# color_proximity_sensor.net
KiCad netlist of a schematic drawn in EAGLE
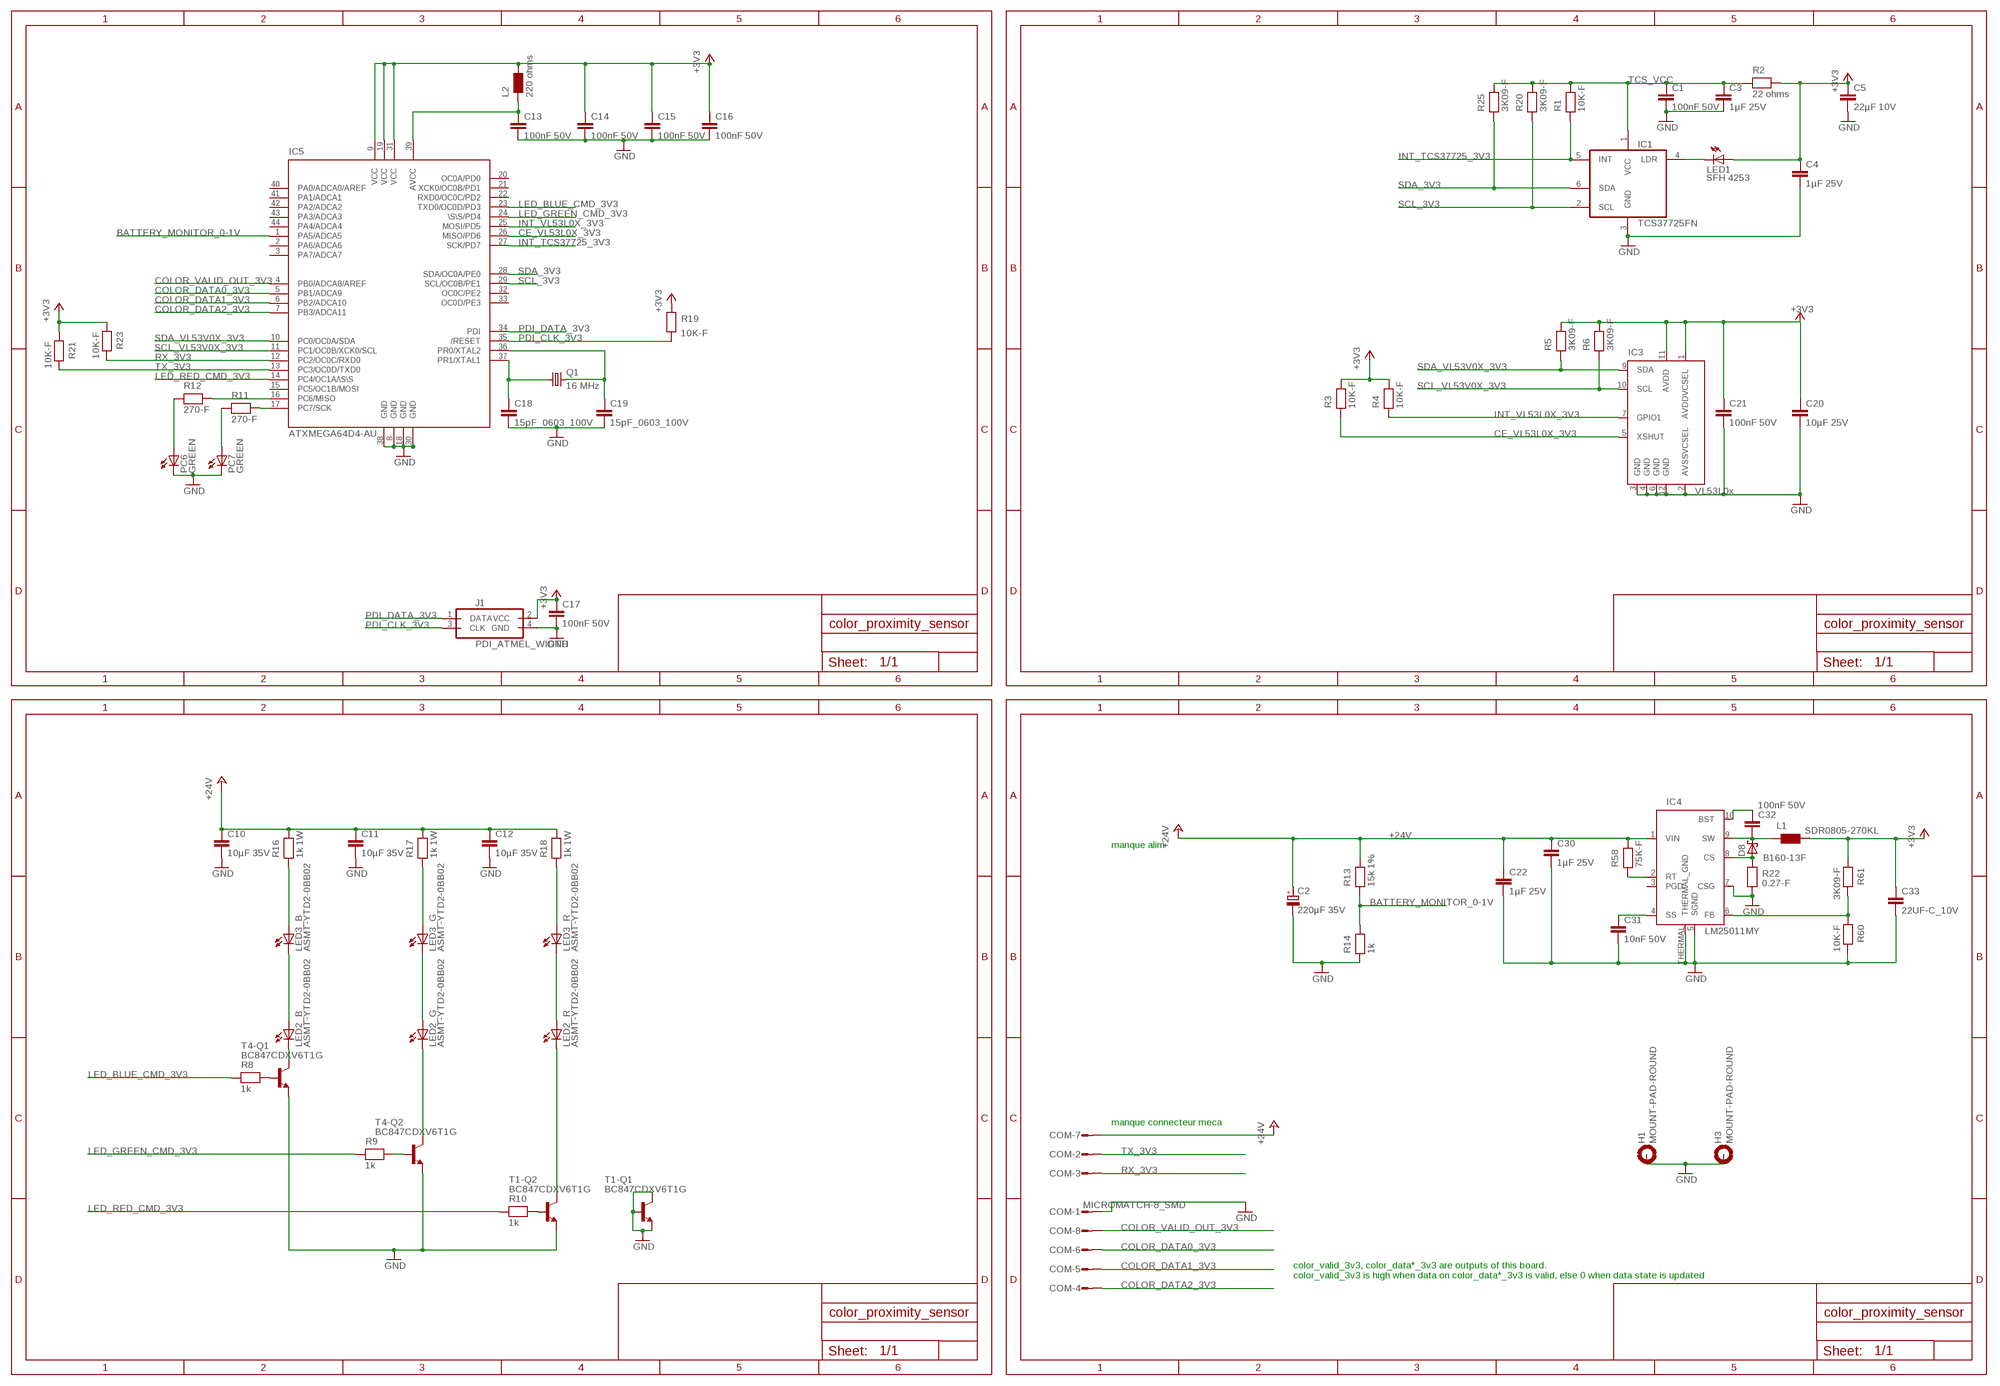
[diagram p0: schematic, sheet 1]

(export (version "E")
  (design (tool "Eeschema 10.0.6"))
  (components
    (comp (ref "C1")
      (value "100nF 50V")
      (footprint "eagle-import:C0603")
      (libsource (lib "eagle-import") (part "100NF-F"))
    )
    (comp (ref "C2")
      (value "220µF 35V")
      (footprint "eagle-import:PANASONIC_F")
      (libsource (lib "eagle-import") (part "220UFF_35V"))
    )
    (comp (ref "C3")
      (value "1µF 25V")
      (footprint "eagle-import:C1206")
      (libsource (lib "eagle-import") (part "1UFD_25V"))
    )
    (comp (ref "C4")
      (value "1µF 25V")
      (footprint "eagle-import:C1206")
      (libsource (lib "eagle-import") (part "1UFD_25V"))
    )
    (comp (ref "C5")
      (value "22µF 10V")
      (footprint "eagle-import:C1210")
      (libsource (lib "eagle-import") (part "22UF-C_10V"))
    )
    (comp (ref "C10")
      (value "10µF 35V")
      (footprint "eagle-import:C1210")
      (libsource (lib "eagle-import") (part "10UF-C_35V"))
    )
    (comp (ref "C11")
      (value "10µF 35V")
      (footprint "eagle-import:C1210")
      (libsource (lib "eagle-import") (part "10UF-C_35V"))
    )
    (comp (ref "C12")
      (value "10µF 35V")
      (footprint "eagle-import:C1210")
      (libsource (lib "eagle-import") (part "10UF-C_35V"))
    )
    (comp (ref "C13")
      (value "100nF 50V")
      (footprint "eagle-import:C0603")
      (libsource (lib "eagle-import") (part "100NF-F"))
    )
    (comp (ref "C14")
      (value "100nF 50V")
      (footprint "eagle-import:C0603")
      (libsource (lib "eagle-import") (part "100NF-F"))
    )
    (comp (ref "C15")
      (value "100nF 50V")
      (footprint "eagle-import:C0603")
      (libsource (lib "eagle-import") (part "100NF-F"))
    )
    (comp (ref "C16")
      (value "100nF 50V")
      (footprint "eagle-import:C0603")
      (libsource (lib "eagle-import") (part "100NF-F"))
    )
    (comp (ref "C17")
      (value "100nF 50V")
      (footprint "eagle-import:C0603")
      (libsource (lib "eagle-import") (part "100NF-F"))
    )
    (comp (ref "C18")
      (value "15pF_0603_100V")
      (footprint "eagle-import:C0603")
      (libsource (lib "eagle-import") (part "15PF-F"))
    )
    (comp (ref "C19")
      (value "15pF_0603_100V")
      (footprint "eagle-import:C0603")
      (libsource (lib "eagle-import") (part "15PF-F"))
    )
    (comp (ref "C20")
      (value "10µF 25V")
      (footprint "eagle-import:C1210")
      (libsource (lib "eagle-import") (part "10UF-C_25V"))
    )
    (comp (ref "C21")
      (value "100nF 50V")
      (footprint "eagle-import:C0603")
      (libsource (lib "eagle-import") (part "100NF-F"))
    )
    (comp (ref "C22")
      (value "1µF 25V")
      (footprint "eagle-import:C1206")
      (libsource (lib "eagle-import") (part "1UFD_25V"))
    )
    (comp (ref "C30")
      (value "1µF 25V")
      (footprint "eagle-import:C1206")
      (libsource (lib "eagle-import") (part "1UFD_25V"))
    )
    (comp (ref "C31")
      (value "10nF 50V")
      (footprint "eagle-import:C0603")
      (libsource (lib "eagle-import") (part "10NF-F"))
    )
    (comp (ref "C32")
      (value "100nF 50V")
      (footprint "eagle-import:C0603")
      (libsource (lib "eagle-import") (part "100NF-F"))
    )
    (comp (ref "C33")
      (value "22UF-C_10V")
      (footprint "eagle-import:C1210")
      (libsource (lib "eagle-import") (part "22UF-C_10V"))
    )
    (comp (ref "COM")
      (value "MICROMATCH-8_SMD")
      (footprint "eagle-import:MICROMATCH-8_SMD")
      (libsource (lib "eagle-import") (part "MICROMATCH-8_SMD"))
    )
    (comp (ref "D8")
      (value "B160-13F")
      (footprint "eagle-import:SMA")
      (libsource (lib "eagle-import") (part "B160-13F"))
    )
    (comp (ref "H1")
      (value "MOUNT-PAD-ROUND")
      (footprint "eagle-import:2,1-PAD")
      (libsource (lib "eagle-import") (part "MOUNT-PAD-ROUND"))
    )
    (comp (ref "H3")
      (value "MOUNT-PAD-ROUND")
      (footprint "eagle-import:2,1-PAD")
      (libsource (lib "eagle-import") (part "MOUNT-PAD-ROUND"))
    )
    (comp (ref "IC1")
      (value "TCS37725FN")
      (footprint "eagle-import:FN6")
      (libsource (lib "eagle-import") (part "TCS37725FN"))
    )
    (comp (ref "IC3")
      (value "VL53L0x")
      (footprint "eagle-import:LGA12")
      (libsource (lib "eagle-import") (part "VL53L0X"))
    )
    (comp (ref "IC4")
      (value "LM25011MY")
      (footprint "eagle-import:MSOP10_THERMAL")
      (libsource (lib "eagle-import") (part "LM25011MY"))
    )
    (comp (ref "IC5")
      (value "ATXMEGA64D4-AU")
      (footprint "eagle-import:TQFP44")
      (libsource (lib "eagle-import") (part "ATXMEGA64D4-AU"))
    )
    (comp (ref "J1")
      (value "PDI_ATMEL_WIDTH")
      (footprint "eagle-import:HEADER_2.54MM_2X2W_")
      (libsource (lib "eagle-import") (part "PDI_ATMEL_WIDTH"))
    )
    (comp (ref "L1")
      (value "SDR0805-270KL")
      (footprint "eagle-import:SDR0805")
      (libsource (lib "eagle-import") (part "SDR0805-270KL"))
    )
    (comp (ref "L2")
      (value "220 ohms")
      (footprint "eagle-import:R0603")
      (libsource (lib "eagle-import") (part "FERRITE_220OHMS"))
    )
    (comp (ref "LED1")
      (value "SFH 4253")
      (footprint "eagle-import:SFH4253")
      (libsource (lib "eagle-import") (part "SFH4253"))
    )
    (comp (ref "LED2")
      (value "ASMT-YTD2-0BB02")
      (footprint "eagle-import:PLCC6")
      (fields (field (name "MANUFACTURER") "AVAGO TECHNOLOGIES"))
      (libsource (lib "eagle-import") (part "LED_MULTICOLOR"))
    )
    (comp (ref "LED3")
      (value "ASMT-YTD2-0BB02")
      (footprint "eagle-import:PLCC6")
      (fields (field (name "MANUFACTURER") "AVAGO TECHNOLOGIES"))
      (libsource (lib "eagle-import") (part "LED_MULTICOLOR"))
    )
    (comp (ref "PC6")
      (value "GREEN")
      (footprint "eagle-import:CHIP-LED0805")
      (libsource (lib "eagle-import") (part "LED_G"))
    )
    (comp (ref "PC7")
      (value "GREEN")
      (footprint "eagle-import:CHIP-LED0805")
      (libsource (lib "eagle-import") (part "LED_G"))
    )
    (comp (ref "Q1")
      (value "16 MHz")
      (footprint "eagle-import:HC49UP")
      (libsource (lib "eagle-import") (part "CRYSTAL_16MHZ_HC49UP"))
    )
    (comp (ref "R1")
      (value "10K-F")
      (footprint "eagle-import:R0603")
      (libsource (lib "eagle-import") (part "10K-F"))
    )
    (comp (ref "R2")
      (value "22 ohms")
      (footprint "eagle-import:R0603")
      (libsource (lib "eagle-import") (part "22-F"))
    )
    (comp (ref "R3")
      (value "10K-F")
      (footprint "eagle-import:R0603")
      (libsource (lib "eagle-import") (part "10K-F"))
    )
    (comp (ref "R4")
      (value "10K-F")
      (footprint "eagle-import:R0603")
      (libsource (lib "eagle-import") (part "10K-F"))
    )
    (comp (ref "R5")
      (value "3K09-F")
      (footprint "eagle-import:R0603")
      (libsource (lib "eagle-import") (part "3K09-F"))
    )
    (comp (ref "R6")
      (value "3K09-F")
      (footprint "eagle-import:R0603")
      (libsource (lib "eagle-import") (part "3K09-F"))
    )
    (comp (ref "R8")
      (value "1k")
      (footprint "eagle-import:R0603")
      (libsource (lib "eagle-import") (part "1K-F"))
    )
    (comp (ref "R9")
      (value "1k")
      (footprint "eagle-import:R0603")
      (libsource (lib "eagle-import") (part "1K-F"))
    )
    (comp (ref "R10")
      (value "1k")
      (footprint "eagle-import:R0603")
      (libsource (lib "eagle-import") (part "1K-F"))
    )
    (comp (ref "R11")
      (value "270-F")
      (footprint "eagle-import:R0603")
      (libsource (lib "eagle-import") (part "270-F"))
    )
    (comp (ref "R12")
      (value "270-F")
      (footprint "eagle-import:R0603")
      (libsource (lib "eagle-import") (part "270-F"))
    )
    (comp (ref "R13")
      (value "15k 1%")
      (footprint "eagle-import:R0805")
      (libsource (lib "eagle-import") (part "15K-E"))
    )
    (comp (ref "R14")
      (value "1k")
      (footprint "eagle-import:R0805")
      (libsource (lib "eagle-import") (part "1K-E"))
    )
    (comp (ref "R16")
      (value "1k 1W")
      (footprint "eagle-import:R2512")
      (libsource (lib "eagle-import") (part "1K-A"))
    )
    (comp (ref "R17")
      (value "1k 1W")
      (footprint "eagle-import:R2512")
      (libsource (lib "eagle-import") (part "1K-A"))
    )
    (comp (ref "R18")
      (value "1k 1W")
      (footprint "eagle-import:R2512")
      (libsource (lib "eagle-import") (part "1K-A"))
    )
    (comp (ref "R19")
      (value "10K-F")
      (footprint "eagle-import:R0603")
      (libsource (lib "eagle-import") (part "10K-F"))
    )
    (comp (ref "R20")
      (value "3K09-F")
      (footprint "eagle-import:R0603")
      (libsource (lib "eagle-import") (part "3K09-F"))
    )
    (comp (ref "R21")
      (value "10K-F")
      (footprint "eagle-import:R0603")
      (libsource (lib "eagle-import") (part "10K-F"))
    )
    (comp (ref "R22")
      (value "0.27-F")
      (footprint "eagle-import:R0603")
      (libsource (lib "eagle-import") (part "0.27-F"))
    )
    (comp (ref "R23")
      (value "10K-F")
      (footprint "eagle-import:R0603")
      (libsource (lib "eagle-import") (part "10K-F"))
    )
    (comp (ref "R25")
      (value "3K09-F")
      (footprint "eagle-import:R0603")
      (libsource (lib "eagle-import") (part "3K09-F"))
    )
    (comp (ref "R58")
      (value "75K-F")
      (footprint "eagle-import:R0603")
      (libsource (lib "eagle-import") (part "75K-F"))
    )
    (comp (ref "R60")
      (value "10K-F")
      (footprint "eagle-import:R0603")
      (libsource (lib "eagle-import") (part "10K-F"))
    )
    (comp (ref "R61")
      (value "3K09-F")
      (footprint "eagle-import:R0603")
      (libsource (lib "eagle-import") (part "3K09-F"))
    )
    (comp (ref "T1")
      (value "BC847CDXV6T1G")
      (footprint "eagle-import:SOT563-6")
      (libsource (lib "eagle-import") (part "BC847CDXV6T"))
    )
    (comp (ref "T4")
      (value "BC847CDXV6T1G")
      (footprint "eagle-import:SOT563-6")
      (libsource (lib "eagle-import") (part "BC847CDXV6T"))
    )
  )
  (nets
    (net (code "1") (name "+3V3") (class "Default")
      (node (ref "C14") (pin "1") (pinfunction "1_1") (pintype "passive"))
      (node (ref "C15") (pin "1") (pinfunction "1_1") (pintype "passive"))
      (node (ref "C16") (pin "1") (pinfunction "1_1") (pintype "passive"))
      (node (ref "C17") (pin "1") (pinfunction "1_1") (pintype "passive"))
      (node (ref "C20") (pin "1") (pinfunction "1_1") (pintype "passive"))
      (node (ref "C21") (pin "1") (pinfunction "1_1") (pintype "passive"))
      (node (ref "C33") (pin "1") (pinfunction "1_1") (pintype "passive"))
      (node (ref "C4") (pin "1") (pinfunction "1_1") (pintype "passive"))
      (node (ref "C5") (pin "1") (pinfunction "1_1") (pintype "passive"))
      (node (ref "IC3") (pin "1") (pinfunction "AVDDVCSEL_1") (pintype "power_in"))
      (node (ref "IC3") (pin "11") (pinfunction "AVDD_11") (pintype "bidirectional"))
      (node (ref "IC5") (pin "19") (pinfunction "VCC_19") (pintype "bidirectional"))
      (node (ref "IC5") (pin "31") (pinfunction "VCC_31") (pintype "bidirectional"))
      (node (ref "IC5") (pin "9") (pinfunction "VCC_9") (pintype "bidirectional"))
      (node (ref "J1") (pin "2") (pinfunction "VCC_2") (pintype "passive"))
      (node (ref "L1") (pin "2") (pinfunction "2_2") (pintype "passive"))
      (node (ref "L2") (pin "2") (pinfunction "2_2") (pintype "passive"))
      (node (ref "LED1") (pin "A") (pinfunction "A_A") (pintype "passive"))
      (node (ref "R19") (pin "2") (pinfunction "2_2") (pintype "bidirectional"))
      (node (ref "R2") (pin "2") (pinfunction "2_2") (pintype "bidirectional"))
      (node (ref "R21") (pin "1") (pinfunction "1_1") (pintype "bidirectional"))
      (node (ref "R23") (pin "1") (pinfunction "1_1") (pintype "bidirectional"))
      (node (ref "R3") (pin "2") (pinfunction "2_2") (pintype "bidirectional"))
      (node (ref "R4") (pin "2") (pinfunction "2_2") (pintype "bidirectional"))
      (node (ref "R5") (pin "2") (pinfunction "2_2") (pintype "bidirectional"))
      (node (ref "R6") (pin "2") (pinfunction "2_2") (pintype "bidirectional"))
      (node (ref "R61") (pin "1") (pinfunction "1_1") (pintype "bidirectional"))
    )
    (net (code "2") (name "+24V") (class "Default")
      (node (ref "C10") (pin "1") (pinfunction "1_1") (pintype "passive"))
      (node (ref "C11") (pin "1") (pinfunction "1_1") (pintype "passive"))
      (node (ref "C12") (pin "1") (pinfunction "1_1") (pintype "passive"))
      (node (ref "C2") (pin "+") (pinfunction "+_+") (pintype "passive"))
      (node (ref "C22") (pin "1") (pinfunction "1_1") (pintype "passive"))
      (node (ref "C30") (pin "1") (pinfunction "1_1") (pintype "passive"))
      (node (ref "COM") (pin "7") (pinfunction "S_7") (pintype "passive"))
      (node (ref "IC4") (pin "1") (pinfunction "VIN_1") (pintype "input"))
      (node (ref "R13") (pin "2") (pinfunction "2_2") (pintype "bidirectional"))
      (node (ref "R16") (pin "2") (pinfunction "2_2") (pintype "bidirectional"))
      (node (ref "R17") (pin "2") (pinfunction "2_2") (pintype "bidirectional"))
      (node (ref "R18") (pin "2") (pinfunction "2_2") (pintype "bidirectional"))
      (node (ref "R58") (pin "2") (pinfunction "2_2") (pintype "bidirectional"))
    )
    (net (code "3") (name "/BATTERY_MONITOR_0-1V") (class "Default")
      (node (ref "IC5") (pin "1") (pinfunction "PA5/ADCA5_1") (pintype "bidirectional"))
      (node (ref "R13") (pin "1") (pinfunction "1_1") (pintype "bidirectional"))
      (node (ref "R14") (pin "2") (pinfunction "2_2") (pintype "bidirectional"))
    )
    (net (code "4") (name "/CE_VL53L0X_3V3") (class "Default")
      (node (ref "IC3") (pin "5") (pinfunction "XSHUT_5") (pintype "bidirectional"))
      (node (ref "IC5") (pin "26") (pinfunction "MISO/PD6_26") (pintype "bidirectional"))
      (node (ref "R3") (pin "1") (pinfunction "1_1") (pintype "bidirectional"))
    )
    (net (code "5") (name "/COLOR_DATA0_3V3") (class "Default")
      (node (ref "COM") (pin "6") (pinfunction "S_6") (pintype "passive"))
      (node (ref "IC5") (pin "5") (pinfunction "PB1/ADCA9_5") (pintype "bidirectional"))
    )
    (net (code "6") (name "/COLOR_DATA1_3V3") (class "Default")
      (node (ref "COM") (pin "5") (pinfunction "S_5") (pintype "passive"))
      (node (ref "IC5") (pin "6") (pinfunction "PB2/ADCA10_6") (pintype "bidirectional"))
    )
    (net (code "7") (name "/COLOR_DATA2_3V3") (class "Default")
      (node (ref "COM") (pin "4") (pinfunction "S_4") (pintype "passive"))
      (node (ref "IC5") (pin "7") (pinfunction "PB3/ADCA11_7") (pintype "bidirectional"))
    )
    (net (code "8") (name "/COLOR_VALID_OUT_3V3") (class "Default")
      (node (ref "COM") (pin "8") (pinfunction "S_8") (pintype "passive"))
      (node (ref "IC5") (pin "4") (pinfunction "PB0/ADCA8/AREF_4") (pintype "bidirectional"))
    )
    (net (code "9") (name "/INT_TCS37725_3V3") (class "Default")
      (node (ref "IC1") (pin "5") (pinfunction "INT_5") (pintype "open_collector"))
      (node (ref "IC5") (pin "27") (pinfunction "SCK/PD7_27") (pintype "bidirectional"))
      (node (ref "R1") (pin "1") (pinfunction "1_1") (pintype "bidirectional"))
    )
    (net (code "10") (name "/INT_VL53L0X_3V3") (class "Default")
      (node (ref "IC3") (pin "7") (pinfunction "GPIO1_7") (pintype "output"))
      (node (ref "IC5") (pin "25") (pinfunction "MOSI/PD5_25") (pintype "bidirectional"))
      (node (ref "R4") (pin "1") (pinfunction "1_1") (pintype "bidirectional"))
    )
    (net (code "11") (name "/LED_BLUE_CMD_3V3") (class "Default")
      (node (ref "IC5") (pin "23") (pinfunction "TXD0/OC0D/PD3_23") (pintype "bidirectional"))
      (node (ref "R8") (pin "1") (pinfunction "1_1") (pintype "bidirectional"))
    )
    (net (code "12") (name "/LED_GREEN_CMD_3V3") (class "Default")
      (node (ref "IC5") (pin "24") (pinfunction "\\S\\S/PD4_24") (pintype "bidirectional"))
      (node (ref "R9") (pin "1") (pinfunction "1_1") (pintype "bidirectional"))
    )
    (net (code "13") (name "/LED_RED_CMD_3V3") (class "Default")
      (node (ref "IC5") (pin "14") (pinfunction "PC4/OC1A/\\S\\S_14") (pintype "bidirectional"))
      (node (ref "R10") (pin "1") (pinfunction "1_1") (pintype "bidirectional"))
    )
    (net (code "14") (name "/PDI_CLK_3V3") (class "Default")
      (node (ref "IC5") (pin "35") (pinfunction "/RESET_35") (pintype "bidirectional"))
      (node (ref "J1") (pin "3") (pinfunction "CLK_3") (pintype "passive"))
      (node (ref "R19") (pin "1") (pinfunction "1_1") (pintype "bidirectional"))
    )
    (net (code "15") (name "/PDI_DATA_3V3") (class "Default")
      (node (ref "IC5") (pin "34") (pinfunction "PDI_34") (pintype "bidirectional"))
      (node (ref "J1") (pin "1") (pinfunction "DATA_1") (pintype "passive"))
    )
    (net (code "16") (name "/RX_3V3") (class "Default")
      (node (ref "COM") (pin "3") (pinfunction "S_3") (pintype "passive"))
      (node (ref "IC5") (pin "12") (pinfunction "PC2/OC0C/RXD0_12") (pintype "bidirectional"))
      (node (ref "R23") (pin "2") (pinfunction "2_2") (pintype "bidirectional"))
    )
    (net (code "17") (name "/SCL_3V3") (class "Default")
      (node (ref "IC1") (pin "2") (pinfunction "SCL_2") (pintype "open_collector"))
      (node (ref "IC5") (pin "29") (pinfunction "SCL/OC0B/PE1_29") (pintype "bidirectional"))
      (node (ref "R20") (pin "1") (pinfunction "1_1") (pintype "bidirectional"))
    )
    (net (code "18") (name "/SCL_VL53V0X_3V3") (class "Default")
      (node (ref "IC3") (pin "10") (pinfunction "SCL_10") (pintype "input"))
      (node (ref "IC5") (pin "11") (pinfunction "PC1/OC0B/XCK0/SCL_11") (pintype "bidirectional"))
      (node (ref "R6") (pin "1") (pinfunction "1_1") (pintype "bidirectional"))
    )
    (net (code "19") (name "/SDA_3V3") (class "Default")
      (node (ref "IC1") (pin "6") (pinfunction "SDA_6") (pintype "open_collector"))
      (node (ref "IC5") (pin "28") (pinfunction "SDA/OC0A/PE0_28") (pintype "bidirectional"))
      (node (ref "R25") (pin "1") (pinfunction "1_1") (pintype "bidirectional"))
    )
    (net (code "20") (name "/SDA_VL53V0X_3V3") (class "Default")
      (node (ref "IC3") (pin "9") (pinfunction "SDA_9") (pintype "bidirectional"))
      (node (ref "IC5") (pin "10") (pinfunction "PC0/OC0A/SDA_10") (pintype "bidirectional"))
      (node (ref "R5") (pin "1") (pinfunction "1_1") (pintype "bidirectional"))
    )
    (net (code "21") (name "/TCS_VCC") (class "Default")
      (node (ref "C1") (pin "1") (pinfunction "1_1") (pintype "passive"))
      (node (ref "C3") (pin "1") (pinfunction "1_1") (pintype "passive"))
      (node (ref "IC1") (pin "1") (pinfunction "VCC_1") (pintype "power_in"))
      (node (ref "R1") (pin "2") (pinfunction "2_2") (pintype "bidirectional"))
      (node (ref "R2") (pin "1") (pinfunction "1_1") (pintype "bidirectional"))
      (node (ref "R20") (pin "2") (pinfunction "2_2") (pintype "bidirectional"))
      (node (ref "R25") (pin "2") (pinfunction "2_2") (pintype "bidirectional"))
    )
    (net (code "22") (name "/TX_3V3") (class "Default")
      (node (ref "COM") (pin "2") (pinfunction "S_2") (pintype "passive"))
      (node (ref "IC5") (pin "13") (pinfunction "PC3/OC0D/TXD0_13") (pintype "bidirectional"))
      (node (ref "R21") (pin "2") (pinfunction "2_2") (pintype "bidirectional"))
    )
    (net (code "23") (name "GND") (class "Default")
      (node (ref "C1") (pin "2") (pinfunction "2_2") (pintype "passive"))
      (node (ref "C10") (pin "2") (pinfunction "2_2") (pintype "passive"))
      (node (ref "C11") (pin "2") (pinfunction "2_2") (pintype "passive"))
      (node (ref "C12") (pin "2") (pinfunction "2_2") (pintype "passive"))
      (node (ref "C13") (pin "2") (pinfunction "2_2") (pintype "passive"))
      (node (ref "C14") (pin "2") (pinfunction "2_2") (pintype "passive"))
      (node (ref "C15") (pin "2") (pinfunction "2_2") (pintype "passive"))
      (node (ref "C16") (pin "2") (pinfunction "2_2") (pintype "passive"))
      (node (ref "C17") (pin "2") (pinfunction "2_2") (pintype "passive"))
      (node (ref "C18") (pin "2") (pinfunction "2_2") (pintype "passive"))
      (node (ref "C19") (pin "2") (pinfunction "2_2") (pintype "passive"))
      (node (ref "C2") (pin "-") (pinfunction "-_-") (pintype "passive"))
      (node (ref "C20") (pin "2") (pinfunction "2_2") (pintype "passive"))
      (node (ref "C21") (pin "2") (pinfunction "2_2") (pintype "passive"))
      (node (ref "C22") (pin "2") (pinfunction "2_2") (pintype "passive"))
      (node (ref "C3") (pin "2") (pinfunction "2_2") (pintype "passive"))
      (node (ref "C30") (pin "2") (pinfunction "2_2") (pintype "passive"))
      (node (ref "C31") (pin "2") (pinfunction "2_2") (pintype "passive"))
      (node (ref "C33") (pin "2") (pinfunction "2_2") (pintype "passive"))
      (node (ref "C4") (pin "2") (pinfunction "2_2") (pintype "passive"))
      (node (ref "C5") (pin "2") (pinfunction "2_2") (pintype "passive"))
      (node (ref "COM") (pin "1") (pinfunction "S_1") (pintype "passive"))
      (node (ref "H1") (pin "B2,8") (pinfunction "MOUNT_B2,8") (pintype "passive"))
      (node (ref "H3") (pin "B2,8") (pinfunction "MOUNT_B2,8") (pintype "passive"))
      (node (ref "IC1") (pin "3") (pinfunction "GND_3") (pintype "power_in"))
      (node (ref "IC3") (pin "12") (pinfunction "GND_12") (pintype "bidirectional"))
      (node (ref "IC3") (pin "2") (pinfunction "AVSSVCSEL_2") (pintype "power_in"))
      (node (ref "IC3") (pin "3") (pinfunction "GND_3") (pintype "bidirectional"))
      (node (ref "IC3") (pin "4") (pinfunction "GND_4") (pintype "bidirectional"))
      (node (ref "IC3") (pin "6") (pinfunction "GND_6") (pintype "bidirectional"))
      (node (ref "IC4") (pin "5") (pinfunction "SGND_5") (pintype "power_in"))
      (node (ref "IC4") (pin "7") (pinfunction "CSG_7") (pintype "input"))
      (node (ref "IC4") (pin "THERMAL") (pinfunction "THERMAL_GND_THERMAL") (pintype "power_in"))
      (node (ref "IC5") (pin "18") (pinfunction "GND_18") (pintype "bidirectional"))
      (node (ref "IC5") (pin "30") (pinfunction "GND_30") (pintype "bidirectional"))
      (node (ref "IC5") (pin "38") (pinfunction "GND_38") (pintype "bidirectional"))
      (node (ref "IC5") (pin "8") (pinfunction "GND_8") (pintype "bidirectional"))
      (node (ref "J1") (pin "4") (pinfunction "GND_4") (pintype "passive"))
      (node (ref "PC6") (pin "C") (pinfunction "C_C") (pintype "passive"))
      (node (ref "PC7") (pin "C") (pinfunction "C_C") (pintype "passive"))
      (node (ref "R14") (pin "1") (pinfunction "1_1") (pintype "bidirectional"))
      (node (ref "R22") (pin "1") (pinfunction "1_1") (pintype "bidirectional"))
      (node (ref "R60") (pin "2") (pinfunction "2_2") (pintype "bidirectional"))
      (node (ref "T1") (pin "1") (pinfunction "E_1") (pintype "passive"))
      (node (ref "T1") (pin "3") (pinfunction "C_3") (pintype "passive"))
      (node (ref "T1") (pin "4") (pinfunction "E_4") (pintype "passive"))
      (node (ref "T1") (pin "5") (pinfunction "B_5") (pintype "passive"))
      (node (ref "T4") (pin "1") (pinfunction "E_1") (pintype "passive"))
      (node (ref "T4") (pin "4") (pinfunction "E_4") (pintype "passive"))
    )
    (net (code "24") (name "Net-(IC1-LDR)") (class "Default")
      (node (ref "IC1") (pin "4") (pinfunction "LDR_4") (pintype "output"))
      (node (ref "LED1") (pin "C") (pinfunction "C_C") (pintype "passive"))
    )
    (net (code "25") (name "Net-(IC4-BST)") (class "Default")
      (node (ref "C32") (pin "1") (pinfunction "1_1") (pintype "passive"))
      (node (ref "IC4") (pin "10") (pinfunction "BST_10") (pintype "input"))
    )
    (net (code "26") (name "Net-(IC4-CS)") (class "Default")
      (node (ref "D8") (pin "A") (pinfunction "A_A") (pintype "passive"))
      (node (ref "IC4") (pin "8") (pinfunction "CS_8") (pintype "output"))
      (node (ref "R22") (pin "2") (pinfunction "2_2") (pintype "bidirectional"))
    )
    (net (code "27") (name "Net-(IC4-FB)") (class "Default")
      (node (ref "IC4") (pin "6") (pinfunction "FB_6") (pintype "input"))
      (node (ref "R60") (pin "1") (pinfunction "1_1") (pintype "bidirectional"))
      (node (ref "R61") (pin "2") (pinfunction "2_2") (pintype "bidirectional"))
    )
    (net (code "28") (name "Net-(IC4-RT)") (class "Default")
      (node (ref "IC4") (pin "2") (pinfunction "RT_2") (pintype "input"))
      (node (ref "R58") (pin "1") (pinfunction "1_1") (pintype "bidirectional"))
    )
    (net (code "29") (name "Net-(IC4-SS)") (class "Default")
      (node (ref "C31") (pin "1") (pinfunction "1_1") (pintype "passive"))
      (node (ref "IC4") (pin "4") (pinfunction "SS_4") (pintype "power_in"))
    )
    (net (code "30") (name "Net-(IC4-SW)") (class "Default")
      (node (ref "C32") (pin "2") (pinfunction "2_2") (pintype "passive"))
      (node (ref "D8") (pin "C") (pinfunction "C_C") (pintype "passive"))
      (node (ref "IC4") (pin "9") (pinfunction "SW_9") (pintype "output"))
      (node (ref "L1") (pin "1") (pinfunction "1_1") (pintype "passive"))
    )
    (net (code "31") (name "Net-(IC5-AVCC)") (class "Default")
      (node (ref "C13") (pin "1") (pinfunction "1_1") (pintype "passive"))
      (node (ref "IC5") (pin "39") (pinfunction "AVCC_39") (pintype "bidirectional"))
      (node (ref "L2") (pin "1") (pinfunction "1_1") (pintype "passive"))
    )
    (net (code "32") (name "Net-(IC5-PC6{slash}MISO)") (class "Default")
      (node (ref "IC5") (pin "16") (pinfunction "PC6/MISO_16") (pintype "bidirectional"))
      (node (ref "R12") (pin "2") (pinfunction "2_2") (pintype "bidirectional"))
    )
    (net (code "33") (name "Net-(IC5-PC7{slash}SCK)") (class "Default")
      (node (ref "IC5") (pin "17") (pinfunction "PC7/SCK_17") (pintype "bidirectional"))
      (node (ref "R11") (pin "2") (pinfunction "2_2") (pintype "bidirectional"))
    )
    (net (code "34") (name "Net-(IC5-PR0{slash}XTAL2)") (class "Default")
      (node (ref "C19") (pin "1") (pinfunction "1_1") (pintype "passive"))
      (node (ref "IC5") (pin "36") (pinfunction "PR0/XTAL2_36") (pintype "bidirectional"))
      (node (ref "Q1") (pin "2") (pinfunction "2_2") (pintype "passive"))
    )
    (net (code "35") (name "Net-(IC5-PR1{slash}XTAL1)") (class "Default")
      (node (ref "C18") (pin "1") (pinfunction "1_1") (pintype "passive"))
      (node (ref "IC5") (pin "37") (pinfunction "PR1/XTAL1_37") (pintype "bidirectional"))
      (node (ref "Q1") (pin "1") (pinfunction "1_1") (pintype "passive"))
    )
    (net (code "36") (name "Net-(LED2A-A)") (class "Default")
      (node (ref "LED2") (pin "6") (pinfunction "A_6") (pintype "passive"))
      (node (ref "LED3") (pin "1") (pinfunction "C_1") (pintype "passive"))
    )
    (net (code "37") (name "Net-(LED2A-C)") (class "Default")
      (node (ref "LED2") (pin "1") (pinfunction "C_1") (pintype "passive"))
      (node (ref "T4") (pin "3") (pinfunction "C_3") (pintype "passive"))
    )
    (net (code "38") (name "Net-(LED2B-A)") (class "Default")
      (node (ref "LED2") (pin "5") (pinfunction "A_5") (pintype "passive"))
      (node (ref "LED3") (pin "2") (pinfunction "C_2") (pintype "passive"))
    )
    (net (code "39") (name "Net-(LED2B-C)") (class "Default")
      (node (ref "LED2") (pin "2") (pinfunction "C_2") (pintype "passive"))
      (node (ref "T4") (pin "6") (pinfunction "C_6") (pintype "passive"))
    )
    (net (code "40") (name "Net-(LED2C-A)") (class "Default")
      (node (ref "LED2") (pin "4") (pinfunction "A_4") (pintype "passive"))
      (node (ref "LED3") (pin "3") (pinfunction "C_3") (pintype "passive"))
    )
    (net (code "41") (name "Net-(LED2C-C)") (class "Default")
      (node (ref "LED2") (pin "3") (pinfunction "C_3") (pintype "passive"))
      (node (ref "T1") (pin "6") (pinfunction "C_6") (pintype "passive"))
    )
    (net (code "42") (name "Net-(LED3A-A)") (class "Default")
      (node (ref "LED3") (pin "6") (pinfunction "A_6") (pintype "passive"))
      (node (ref "R16") (pin "1") (pinfunction "1_1") (pintype "bidirectional"))
    )
    (net (code "43") (name "Net-(LED3B-A)") (class "Default")
      (node (ref "LED3") (pin "5") (pinfunction "A_5") (pintype "passive"))
      (node (ref "R17") (pin "1") (pinfunction "1_1") (pintype "bidirectional"))
    )
    (net (code "44") (name "Net-(LED3C-A)") (class "Default")
      (node (ref "LED3") (pin "4") (pinfunction "A_4") (pintype "passive"))
      (node (ref "R18") (pin "1") (pinfunction "1_1") (pintype "bidirectional"))
    )
    (net (code "45") (name "Net-(PC6-PadA)") (class "Default")
      (node (ref "PC6") (pin "A") (pinfunction "A_A") (pintype "passive"))
      (node (ref "R12") (pin "1") (pinfunction "1_1") (pintype "bidirectional"))
    )
    (net (code "46") (name "Net-(PC7-PadA)") (class "Default")
      (node (ref "PC7") (pin "A") (pinfunction "A_A") (pintype "passive"))
      (node (ref "R11") (pin "1") (pinfunction "1_1") (pintype "bidirectional"))
    )
    (net (code "47") (name "Net-(T1B-B)") (class "Default")
      (node (ref "R10") (pin "2") (pinfunction "2_2") (pintype "bidirectional"))
      (node (ref "T1") (pin "2") (pinfunction "B_2") (pintype "passive"))
    )
    (net (code "48") (name "Net-(T4A-B)") (class "Default")
      (node (ref "R8") (pin "2") (pinfunction "2_2") (pintype "bidirectional"))
      (node (ref "T4") (pin "5") (pinfunction "B_5") (pintype "passive"))
    )
    (net (code "49") (name "Net-(T4B-B)") (class "Default")
      (node (ref "R9") (pin "2") (pinfunction "2_2") (pintype "bidirectional"))
      (node (ref "T4") (pin "2") (pinfunction "B_2") (pintype "passive"))
    )
    (net (code "50") (name "unconnected-(IC4-PGD-Pad3)") (class "Default")
      (node (ref "IC4") (pin "3") (pinfunction "PGD_3") (pintype "input"))
    )
    (net (code "51") (name "unconnected-(IC5-OC0A{slash}PD0-Pad20)") (class "Default")
      (node (ref "IC5") (pin "20") (pinfunction "OC0A/PD0_20") (pintype "bidirectional"))
    )
    (net (code "52") (name "unconnected-(IC5-OC0C{slash}PE2-Pad32)") (class "Default")
      (node (ref "IC5") (pin "32") (pinfunction "OC0C/PE2_32") (pintype "bidirectional"))
    )
    (net (code "53") (name "unconnected-(IC5-OC0D{slash}PE3-Pad33)") (class "Default")
      (node (ref "IC5") (pin "33") (pinfunction "OC0D/PE3_33") (pintype "bidirectional"))
    )
    (net (code "54") (name "unconnected-(IC5-PA0{slash}ADCA0{slash}AREF-Pad40)") (class "Default")
      (node (ref "IC5") (pin "40") (pinfunction "PA0/ADCA0/AREF_40") (pintype "bidirectional"))
    )
    (net (code "55") (name "unconnected-(IC5-PA1{slash}ADCA1-Pad41)") (class "Default")
      (node (ref "IC5") (pin "41") (pinfunction "PA1/ADCA1_41") (pintype "bidirectional"))
    )
    (net (code "56") (name "unconnected-(IC5-PA2{slash}ADCA2-Pad42)") (class "Default")
      (node (ref "IC5") (pin "42") (pinfunction "PA2/ADCA2_42") (pintype "bidirectional"))
    )
    (net (code "57") (name "unconnected-(IC5-PA3{slash}ADCA3-Pad43)") (class "Default")
      (node (ref "IC5") (pin "43") (pinfunction "PA3/ADCA3_43") (pintype "bidirectional"))
    )
    (net (code "58") (name "unconnected-(IC5-PA4{slash}ADCA4-Pad44)") (class "Default")
      (node (ref "IC5") (pin "44") (pinfunction "PA4/ADCA4_44") (pintype "bidirectional"))
    )
    (net (code "59") (name "unconnected-(IC5-PA6{slash}ADCA6-Pad2)") (class "Default")
      (node (ref "IC5") (pin "2") (pinfunction "PA6/ADCA6_2") (pintype "bidirectional"))
    )
    (net (code "60") (name "unconnected-(IC5-PA7{slash}ADCA7-Pad3)") (class "Default")
      (node (ref "IC5") (pin "3") (pinfunction "PA7/ADCA7_3") (pintype "bidirectional"))
    )
    (net (code "61") (name "unconnected-(IC5-PC5{slash}OC1B{slash}MOSI-Pad15)") (class "Default")
      (node (ref "IC5") (pin "15") (pinfunction "PC5/OC1B/MOSI_15") (pintype "bidirectional"))
    )
    (net (code "62") (name "unconnected-(IC5-RXD0{slash}OC0C{slash}PD2-Pad22)") (class "Default")
      (node (ref "IC5") (pin "22") (pinfunction "RXD0/OC0C/PD2_22") (pintype "bidirectional"))
    )
    (net (code "63") (name "unconnected-(IC5-XCK0{slash}OC0B{slash}PD1-Pad21)") (class "Default")
      (node (ref "IC5") (pin "21") (pinfunction "XCK0/OC0B/PD1_21") (pintype "bidirectional"))
    )
  )
)
